# Dachmodul-KS.net
KiCad netlist of a schematic drawn in EAGLE
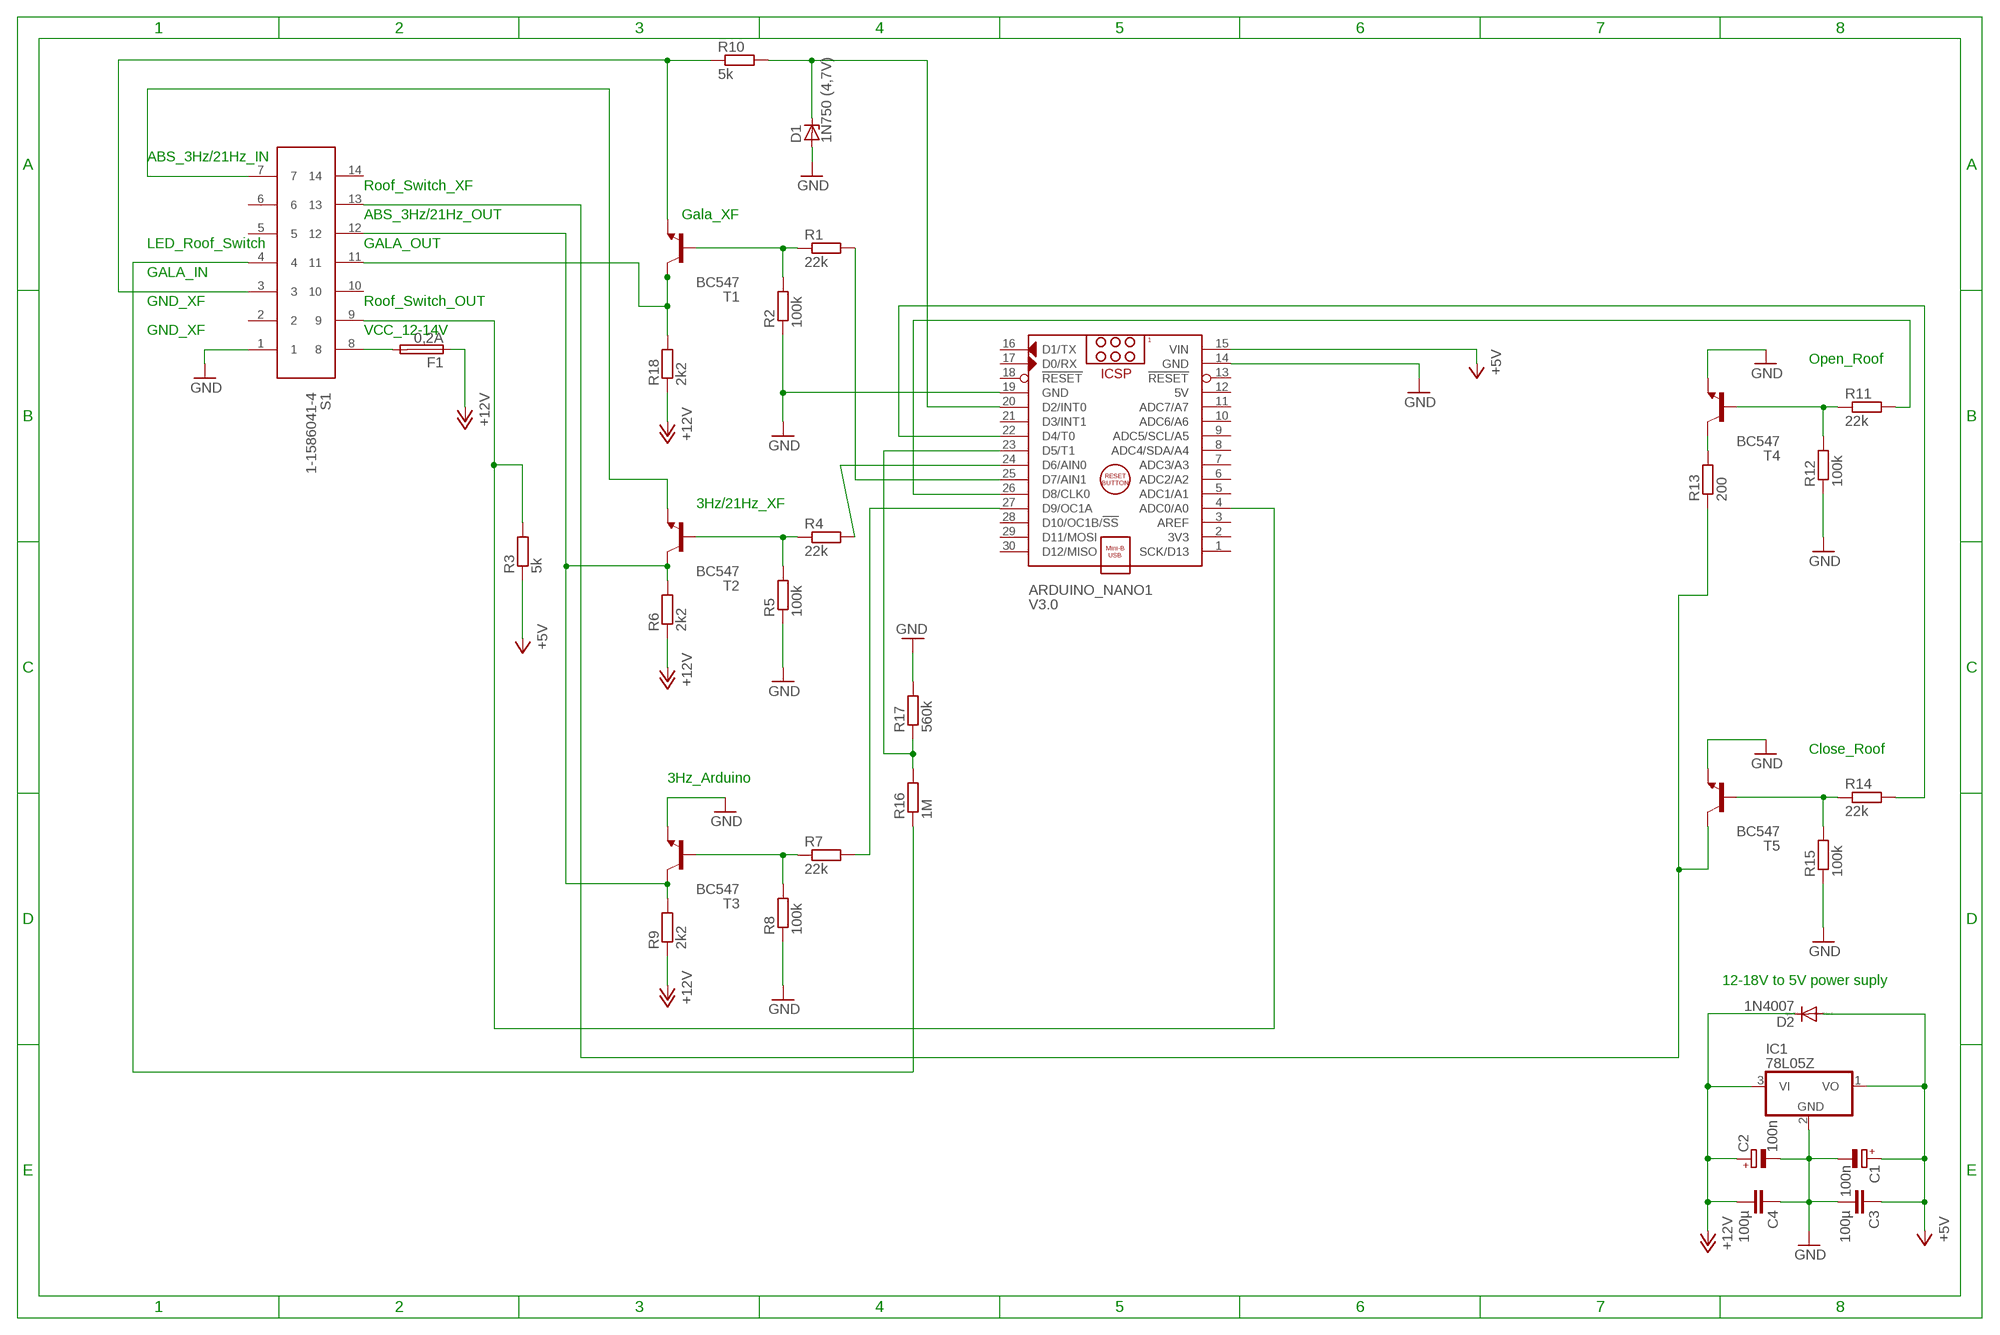
[diagram p0: schematic, sheet 1]

(export (version "E")
  (design (tool "Eeschema 10.0.6"))
  (components
    (comp (ref "ARDUINO_NANO1")
      (value "V3.0")
      (footprint "eagle-import:ARDUINO_NANO")
      (libsource (lib "eagle-import") (part "ARDUINO_NANO"))
    )
    (comp (ref "C1")
      (value "100n")
      (footprint "eagle-import:E3,5-8")
      (libsource (lib "eagle-import") (part "CPOL-EUE3.5-8"))
    )
    (comp (ref "C2")
      (value "100n")
      (footprint "eagle-import:E3,5-8")
      (libsource (lib "eagle-import") (part "CPOL-EUE3.5-8"))
    )
    (comp (ref "C3")
      (value "100µ")
      (footprint "eagle-import:C025-025X050")
      (libsource (lib "eagle-import") (part "C-EU025-025X050"))
    )
    (comp (ref "C4")
      (value "100µ")
      (footprint "eagle-import:C025-025X050")
      (libsource (lib "eagle-import") (part "C-EU025-025X050"))
    )
    (comp (ref "D1")
      (value "1N750 (4,7V)")
      (footprint "eagle-import:ZDIO-2.5")
      (libsource (lib "eagle-import") (part "ZENER-DIODEZD-2.5"))
    )
    (comp (ref "D2")
      (value "1N4007")
      (footprint "eagle-import:DO41-10")
      (libsource (lib "eagle-import") (part "1N4004"))
    )
    (comp (ref "F1")
      (value "0,2A")
      (footprint "eagle-import:SH22,5A")
      (fields (field (name "MPN") "0031.7701.11"))
      (libsource (lib "eagle-import") (part "SH22,5A"))
    )
    (comp (ref "IC1")
      (value "78L05Z")
      (footprint "eagle-import:TO92")
      (libsource (lib "eagle-import") (part "78ZL05"))
    )
    (comp (ref "R1")
      (value "22k")
      (footprint "eagle-import:0207_10")
      (libsource (lib "eagle-import") (part "R-EU_0207/10"))
    )
    (comp (ref "R2")
      (value "100k")
      (footprint "eagle-import:0207_10")
      (libsource (lib "eagle-import") (part "R-EU_0207/10"))
    )
    (comp (ref "R3")
      (value "5k")
      (footprint "eagle-import:0207_10")
      (libsource (lib "eagle-import") (part "R-EU_0207/10"))
    )
    (comp (ref "R4")
      (value "22k")
      (footprint "eagle-import:0207_10")
      (libsource (lib "eagle-import") (part "R-EU_0207/10"))
    )
    (comp (ref "R5")
      (value "100k")
      (footprint "eagle-import:0207_10")
      (libsource (lib "eagle-import") (part "R-EU_0207/10"))
    )
    (comp (ref "R6")
      (value "2k2")
      (footprint "eagle-import:0207_10")
      (libsource (lib "eagle-import") (part "R-EU_0207/10"))
    )
    (comp (ref "R7")
      (value "22k")
      (footprint "eagle-import:0207_10")
      (libsource (lib "eagle-import") (part "R-EU_0207/10"))
    )
    (comp (ref "R8")
      (value "100k")
      (footprint "eagle-import:0207_10")
      (libsource (lib "eagle-import") (part "R-EU_0207/10"))
    )
    (comp (ref "R9")
      (value "2k2")
      (footprint "eagle-import:0207_10")
      (libsource (lib "eagle-import") (part "R-EU_0207/10"))
    )
    (comp (ref "R10")
      (value "5k")
      (footprint "eagle-import:0207_10")
      (libsource (lib "eagle-import") (part "R-EU_0207/10"))
    )
    (comp (ref "R11")
      (value "22k")
      (footprint "eagle-import:0207_10")
      (libsource (lib "eagle-import") (part "R-EU_0207/10"))
    )
    (comp (ref "R12")
      (value "100k")
      (footprint "eagle-import:0207_10")
      (libsource (lib "eagle-import") (part "R-EU_0207/10"))
    )
    (comp (ref "R13")
      (value "200")
      (footprint "eagle-import:0207_10")
      (libsource (lib "eagle-import") (part "R-EU_0207/10"))
    )
    (comp (ref "R14")
      (value "22k")
      (footprint "eagle-import:0207_10")
      (libsource (lib "eagle-import") (part "R-EU_0207/10"))
    )
    (comp (ref "R15")
      (value "100k")
      (footprint "eagle-import:0207_10")
      (libsource (lib "eagle-import") (part "R-EU_0207/10"))
    )
    (comp (ref "R16")
      (value "1M")
      (footprint "eagle-import:0207_10")
      (libsource (lib "eagle-import") (part "R-EU_0207/10"))
    )
    (comp (ref "R17")
      (value "560k")
      (footprint "eagle-import:0207_10")
      (libsource (lib "eagle-import") (part "R-EU_0207/10"))
    )
    (comp (ref "R18")
      (value "2k2")
      (footprint "eagle-import:0207_10")
      (libsource (lib "eagle-import") (part "R-EU_0207/10"))
    )
    (comp (ref "S1")
      (value "1-1586041-4")
      (footprint "eagle-import:64901421022")
      (libsource (lib "eagle-import") (part "64901421022"))
    )
    (comp (ref "T1")
      (value "BC547")
      (footprint "eagle-import:TO92")
      (libsource (lib "eagle-import") (part "BC547"))
    )
    (comp (ref "T2")
      (value "BC547")
      (footprint "eagle-import:TO92")
      (libsource (lib "eagle-import") (part "BC547"))
    )
    (comp (ref "T3")
      (value "BC547")
      (footprint "eagle-import:TO92")
      (libsource (lib "eagle-import") (part "BC547"))
    )
    (comp (ref "T4")
      (value "BC547")
      (footprint "eagle-import:TO92")
      (libsource (lib "eagle-import") (part "BC547"))
    )
    (comp (ref "T5")
      (value "BC547")
      (footprint "eagle-import:TO92")
      (libsource (lib "eagle-import") (part "BC547"))
    )
  )
  (nets
    (net (code "1") (name "+5V") (class "Default")
      (node (ref "ARDUINO_NANO1") (pin "15") (pinfunction "VIN_15") (pintype "power_in"))
      (node (ref "C1") (pin "+") (pinfunction "+_+") (pintype "passive"))
      (node (ref "C3") (pin "1") (pinfunction "1_1") (pintype "passive"))
      (node (ref "D2") (pin "A") (pinfunction "A_A") (pintype "passive"))
      (node (ref "IC1") (pin "1") (pinfunction "VO_1") (pintype "passive"))
      (node (ref "R3") (pin "1") (pinfunction "1_1") (pintype "passive"))
    )
    (net (code "2") (name "+12V") (class "Default")
      (node (ref "C2") (pin "+") (pinfunction "+_+") (pintype "passive"))
      (node (ref "C4") (pin "2") (pinfunction "2_2") (pintype "passive"))
      (node (ref "D2") (pin "C") (pinfunction "C_C") (pintype "passive"))
      (node (ref "F1") (pin "1") (pinfunction "1_1") (pintype "passive"))
      (node (ref "IC1") (pin "3") (pinfunction "VI_3") (pintype "input"))
      (node (ref "R18") (pin "1") (pinfunction "1_1") (pintype "passive"))
      (node (ref "R6") (pin "1") (pinfunction "1_1") (pintype "passive"))
      (node (ref "R9") (pin "1") (pinfunction "1_1") (pintype "passive"))
    )
    (net (code "3") (name "/5V") (class "Default")
      (node (ref "ARDUINO_NANO1") (pin "12") (pinfunction "5V_12") (pintype "power_in"))
    )
    (net (code "4") (name "GND") (class "Default")
      (node (ref "ARDUINO_NANO1") (pin "14") (pinfunction "GND_14") (pintype "power_in"))
      (node (ref "ARDUINO_NANO1") (pin "19") (pinfunction "GND_19") (pintype "power_in"))
      (node (ref "C1") (pin "-") (pinfunction "-_-") (pintype "passive"))
      (node (ref "C2") (pin "-") (pinfunction "-_-") (pintype "passive"))
      (node (ref "C3") (pin "2") (pinfunction "2_2") (pintype "passive"))
      (node (ref "C4") (pin "1") (pinfunction "1_1") (pintype "passive"))
      (node (ref "D1") (pin "A") (pinfunction "A_A") (pintype "passive"))
      (node (ref "IC1") (pin "2") (pinfunction "GND_2") (pintype "passive"))
      (node (ref "R12") (pin "1") (pinfunction "1_1") (pintype "passive"))
      (node (ref "R15") (pin "1") (pinfunction "1_1") (pintype "passive"))
      (node (ref "R17") (pin "2") (pinfunction "2_2") (pintype "passive"))
      (node (ref "R2") (pin "1") (pinfunction "1_1") (pintype "passive"))
      (node (ref "R5") (pin "1") (pinfunction "1_1") (pintype "passive"))
      (node (ref "R8") (pin "1") (pinfunction "1_1") (pintype "passive"))
      (node (ref "S1") (pin "1") (pinfunction "1_1") (pintype "bidirectional"))
      (node (ref "T3") (pin "1") (pinfunction "E_1") (pintype "passive"))
      (node (ref "T4") (pin "1") (pinfunction "E_1") (pintype "passive"))
      (node (ref "T5") (pin "1") (pinfunction "E_1") (pintype "passive"))
    )
    (net (code "5") (name "Net-(ARDUINO_NANO1-ADC0{slash}A0)") (class "Default")
      (node (ref "ARDUINO_NANO1") (pin "4") (pinfunction "ADC0/A0_4") (pintype "bidirectional"))
      (node (ref "R3") (pin "2") (pinfunction "2_2") (pintype "passive"))
      (node (ref "S1") (pin "9") (pinfunction "9_9") (pintype "bidirectional"))
    )
    (net (code "6") (name "Net-(ARDUINO_NANO1-D2{slash}INT0)") (class "Default")
      (node (ref "ARDUINO_NANO1") (pin "20") (pinfunction "D2/INT0_20") (pintype "bidirectional"))
      (node (ref "D1") (pin "C") (pinfunction "C_C") (pintype "passive"))
      (node (ref "R10") (pin "2") (pinfunction "2_2") (pintype "passive"))
    )
    (net (code "7") (name "Net-(ARDUINO_NANO1-D4{slash}T0)") (class "Default")
      (node (ref "ARDUINO_NANO1") (pin "22") (pinfunction "D4/T0_22") (pintype "bidirectional"))
      (node (ref "R14") (pin "2") (pinfunction "2_2") (pintype "passive"))
    )
    (net (code "8") (name "Net-(ARDUINO_NANO1-D5{slash}T1)") (class "Default")
      (node (ref "ARDUINO_NANO1") (pin "23") (pinfunction "D5/T1_23") (pintype "bidirectional"))
      (node (ref "R16") (pin "2") (pinfunction "2_2") (pintype "passive"))
      (node (ref "R17") (pin "1") (pinfunction "1_1") (pintype "passive"))
    )
    (net (code "9") (name "Net-(ARDUINO_NANO1-D6{slash}AIN0)") (class "Default")
      (node (ref "ARDUINO_NANO1") (pin "24") (pinfunction "D6/AIN0_24") (pintype "bidirectional"))
      (node (ref "R4") (pin "2") (pinfunction "2_2") (pintype "passive"))
    )
    (net (code "10") (name "Net-(ARDUINO_NANO1-D7{slash}AIN1)") (class "Default")
      (node (ref "ARDUINO_NANO1") (pin "25") (pinfunction "D7/AIN1_25") (pintype "bidirectional"))
      (node (ref "R1") (pin "2") (pinfunction "2_2") (pintype "passive"))
    )
    (net (code "11") (name "Net-(ARDUINO_NANO1-D8{slash}CLK0)") (class "Default")
      (node (ref "ARDUINO_NANO1") (pin "26") (pinfunction "D8/CLK0_26") (pintype "bidirectional"))
      (node (ref "R11") (pin "2") (pinfunction "2_2") (pintype "passive"))
    )
    (net (code "12") (name "Net-(ARDUINO_NANO1-D9{slash}OC1A)") (class "Default")
      (node (ref "ARDUINO_NANO1") (pin "27") (pinfunction "D9/OC1A_27") (pintype "bidirectional"))
      (node (ref "R7") (pin "2") (pinfunction "2_2") (pintype "passive"))
    )
    (net (code "13") (name "Net-(F1-Pad2)") (class "Default")
      (node (ref "F1") (pin "2") (pinfunction "2_2") (pintype "passive"))
      (node (ref "S1") (pin "8") (pinfunction "8_8") (pintype "bidirectional"))
    )
    (net (code "14") (name "Net-(R16-Pad1)") (class "Default")
      (node (ref "R16") (pin "1") (pinfunction "1_1") (pintype "passive"))
      (node (ref "S1") (pin "4") (pinfunction "4_4") (pintype "bidirectional"))
    )
    (net (code "15") (name "Net-(T1-B)") (class "Default")
      (node (ref "R1") (pin "1") (pinfunction "1_1") (pintype "passive"))
      (node (ref "R2") (pin "2") (pinfunction "2_2") (pintype "passive"))
      (node (ref "T1") (pin "2") (pinfunction "B_2") (pintype "passive"))
    )
    (net (code "16") (name "Net-(T1-C)") (class "Default")
      (node (ref "R18") (pin "2") (pinfunction "2_2") (pintype "passive"))
      (node (ref "S1") (pin "11") (pinfunction "11_11") (pintype "bidirectional"))
      (node (ref "T1") (pin "3") (pinfunction "C_3") (pintype "passive"))
    )
    (net (code "17") (name "Net-(T1-E)") (class "Default")
      (node (ref "R10") (pin "1") (pinfunction "1_1") (pintype "passive"))
      (node (ref "S1") (pin "3") (pinfunction "3_3") (pintype "bidirectional"))
      (node (ref "T1") (pin "1") (pinfunction "E_1") (pintype "passive"))
    )
    (net (code "18") (name "Net-(T2-B)") (class "Default")
      (node (ref "R4") (pin "1") (pinfunction "1_1") (pintype "passive"))
      (node (ref "R5") (pin "2") (pinfunction "2_2") (pintype "passive"))
      (node (ref "T2") (pin "2") (pinfunction "B_2") (pintype "passive"))
    )
    (net (code "19") (name "Net-(T2-C)") (class "Default")
      (node (ref "R6") (pin "2") (pinfunction "2_2") (pintype "passive"))
      (node (ref "R9") (pin "2") (pinfunction "2_2") (pintype "passive"))
      (node (ref "S1") (pin "12") (pinfunction "12_12") (pintype "bidirectional"))
      (node (ref "T2") (pin "3") (pinfunction "C_3") (pintype "passive"))
      (node (ref "T3") (pin "3") (pinfunction "C_3") (pintype "passive"))
    )
    (net (code "20") (name "Net-(T2-E)") (class "Default")
      (node (ref "S1") (pin "7") (pinfunction "7_7") (pintype "bidirectional"))
      (node (ref "T2") (pin "1") (pinfunction "E_1") (pintype "passive"))
    )
    (net (code "21") (name "Net-(T3-B)") (class "Default")
      (node (ref "R7") (pin "1") (pinfunction "1_1") (pintype "passive"))
      (node (ref "R8") (pin "2") (pinfunction "2_2") (pintype "passive"))
      (node (ref "T3") (pin "2") (pinfunction "B_2") (pintype "passive"))
    )
    (net (code "22") (name "Net-(T4-B)") (class "Default")
      (node (ref "R11") (pin "1") (pinfunction "1_1") (pintype "passive"))
      (node (ref "R12") (pin "2") (pinfunction "2_2") (pintype "passive"))
      (node (ref "T4") (pin "2") (pinfunction "B_2") (pintype "passive"))
    )
    (net (code "23") (name "Net-(T4-C)") (class "Default")
      (node (ref "R13") (pin "2") (pinfunction "2_2") (pintype "passive"))
      (node (ref "T4") (pin "3") (pinfunction "C_3") (pintype "passive"))
    )
    (net (code "24") (name "Net-(T5-B)") (class "Default")
      (node (ref "R14") (pin "1") (pinfunction "1_1") (pintype "passive"))
      (node (ref "R15") (pin "2") (pinfunction "2_2") (pintype "passive"))
      (node (ref "T5") (pin "2") (pinfunction "B_2") (pintype "passive"))
    )
    (net (code "25") (name "Net-(T5-C)") (class "Default")
      (node (ref "R13") (pin "1") (pinfunction "1_1") (pintype "passive"))
      (node (ref "S1") (pin "13") (pinfunction "13_13") (pintype "bidirectional"))
      (node (ref "T5") (pin "3") (pinfunction "C_3") (pintype "passive"))
    )
    (net (code "26") (name "unconnected-(ARDUINO_NANO1-3V3-Pad2)") (class "Default")
      (node (ref "ARDUINO_NANO1") (pin "2") (pinfunction "3V3_2") (pintype "output"))
    )
    (net (code "27") (name "unconnected-(ARDUINO_NANO1-ADC1{slash}A1-Pad5)") (class "Default")
      (node (ref "ARDUINO_NANO1") (pin "5") (pinfunction "ADC1/A1_5") (pintype "bidirectional"))
    )
    (net (code "28") (name "unconnected-(ARDUINO_NANO1-ADC2{slash}A2-Pad6)") (class "Default")
      (node (ref "ARDUINO_NANO1") (pin "6") (pinfunction "ADC2/A2_6") (pintype "bidirectional"))
    )
    (net (code "29") (name "unconnected-(ARDUINO_NANO1-ADC3{slash}A3-Pad7)") (class "Default")
      (node (ref "ARDUINO_NANO1") (pin "7") (pinfunction "ADC3/A3_7") (pintype "bidirectional"))
    )
    (net (code "30") (name "unconnected-(ARDUINO_NANO1-ADC4{slash}SDA{slash}A4-Pad8)") (class "Default")
      (node (ref "ARDUINO_NANO1") (pin "8") (pinfunction "ADC4/SDA/A4_8") (pintype "bidirectional"))
    )
    (net (code "31") (name "unconnected-(ARDUINO_NANO1-ADC5{slash}SCL{slash}A5-Pad9)") (class "Default")
      (node (ref "ARDUINO_NANO1") (pin "9") (pinfunction "ADC5/SCL/A5_9") (pintype "bidirectional"))
    )
    (net (code "32") (name "unconnected-(ARDUINO_NANO1-ADC6{slash}A6-Pad10)") (class "Default")
      (node (ref "ARDUINO_NANO1") (pin "10") (pinfunction "ADC6/A6_10") (pintype "bidirectional"))
    )
    (net (code "33") (name "unconnected-(ARDUINO_NANO1-ADC7{slash}A7-Pad11)") (class "Default")
      (node (ref "ARDUINO_NANO1") (pin "11") (pinfunction "ADC7/A7_11") (pintype "bidirectional"))
    )
    (net (code "34") (name "unconnected-(ARDUINO_NANO1-AREF-Pad3)") (class "Default")
      (node (ref "ARDUINO_NANO1") (pin "3") (pinfunction "AREF_3") (pintype "input"))
    )
    (net (code "35") (name "unconnected-(ARDUINO_NANO1-D0{slash}RX-Pad17)") (class "Default")
      (node (ref "ARDUINO_NANO1") (pin "17") (pinfunction "D0/RX_17") (pintype "bidirectional"))
    )
    (net (code "36") (name "unconnected-(ARDUINO_NANO1-D1{slash}TX-Pad16)") (class "Default")
      (node (ref "ARDUINO_NANO1") (pin "16") (pinfunction "D1/TX_16") (pintype "bidirectional"))
    )
    (net (code "37") (name "unconnected-(ARDUINO_NANO1-D3{slash}INT1-Pad21)") (class "Default")
      (node (ref "ARDUINO_NANO1") (pin "21") (pinfunction "D3/INT1_21") (pintype "bidirectional"))
    )
    (net (code "38") (name "unconnected-(ARDUINO_NANO1-D10{slash}OC1B{slash}~{SS}-Pad28)") (class "Default")
      (node (ref "ARDUINO_NANO1") (pin "28") (pinfunction "D10/OC1B/~{SS}_28") (pintype "bidirectional"))
    )
    (net (code "39") (name "unconnected-(ARDUINO_NANO1-D11{slash}MOSI-Pad29)") (class "Default")
      (node (ref "ARDUINO_NANO1") (pin "29") (pinfunction "D11/MOSI_29") (pintype "bidirectional"))
    )
    (net (code "40") (name "unconnected-(ARDUINO_NANO1-D12{slash}MISO-Pad30)") (class "Default")
      (node (ref "ARDUINO_NANO1") (pin "30") (pinfunction "D12/MISO_30") (pintype "bidirectional"))
    )
    (net (code "41") (name "unconnected-(ARDUINO_NANO1-SCK{slash}D13-Pad1)") (class "Default")
      (node (ref "ARDUINO_NANO1") (pin "1") (pinfunction "SCK/D13_1") (pintype "bidirectional"))
    )
    (net (code "42") (name "unconnected-(ARDUINO_NANO1-~{RESET}-Pad13)") (class "Default")
      (node (ref "ARDUINO_NANO1") (pin "13") (pinfunction "~{RESET}_13") (pintype "input"))
    )
    (net (code "43") (name "unconnected-(ARDUINO_NANO1-~{RESET}-Pad18)") (class "Default")
      (node (ref "ARDUINO_NANO1") (pin "18") (pinfunction "~{RESET}_18") (pintype "input"))
    )
    (net (code "44") (name "unconnected-(S1-Pad2)") (class "Default")
      (node (ref "S1") (pin "2") (pinfunction "2_2") (pintype "bidirectional"))
    )
    (net (code "45") (name "unconnected-(S1-Pad5)") (class "Default")
      (node (ref "S1") (pin "5") (pinfunction "5_5") (pintype "bidirectional"))
    )
    (net (code "46") (name "unconnected-(S1-Pad6)") (class "Default")
      (node (ref "S1") (pin "6") (pinfunction "6_6") (pintype "bidirectional"))
    )
    (net (code "47") (name "unconnected-(S1-Pad10)") (class "Default")
      (node (ref "S1") (pin "10") (pinfunction "10_10") (pintype "bidirectional"))
    )
    (net (code "48") (name "unconnected-(S1-Pad14)") (class "Default")
      (node (ref "S1") (pin "14") (pinfunction "14_14") (pintype "bidirectional"))
    )
  )
)
